# Populated_PLG_sensor.net
KiCad netlist of a schematic drawn in EAGLE
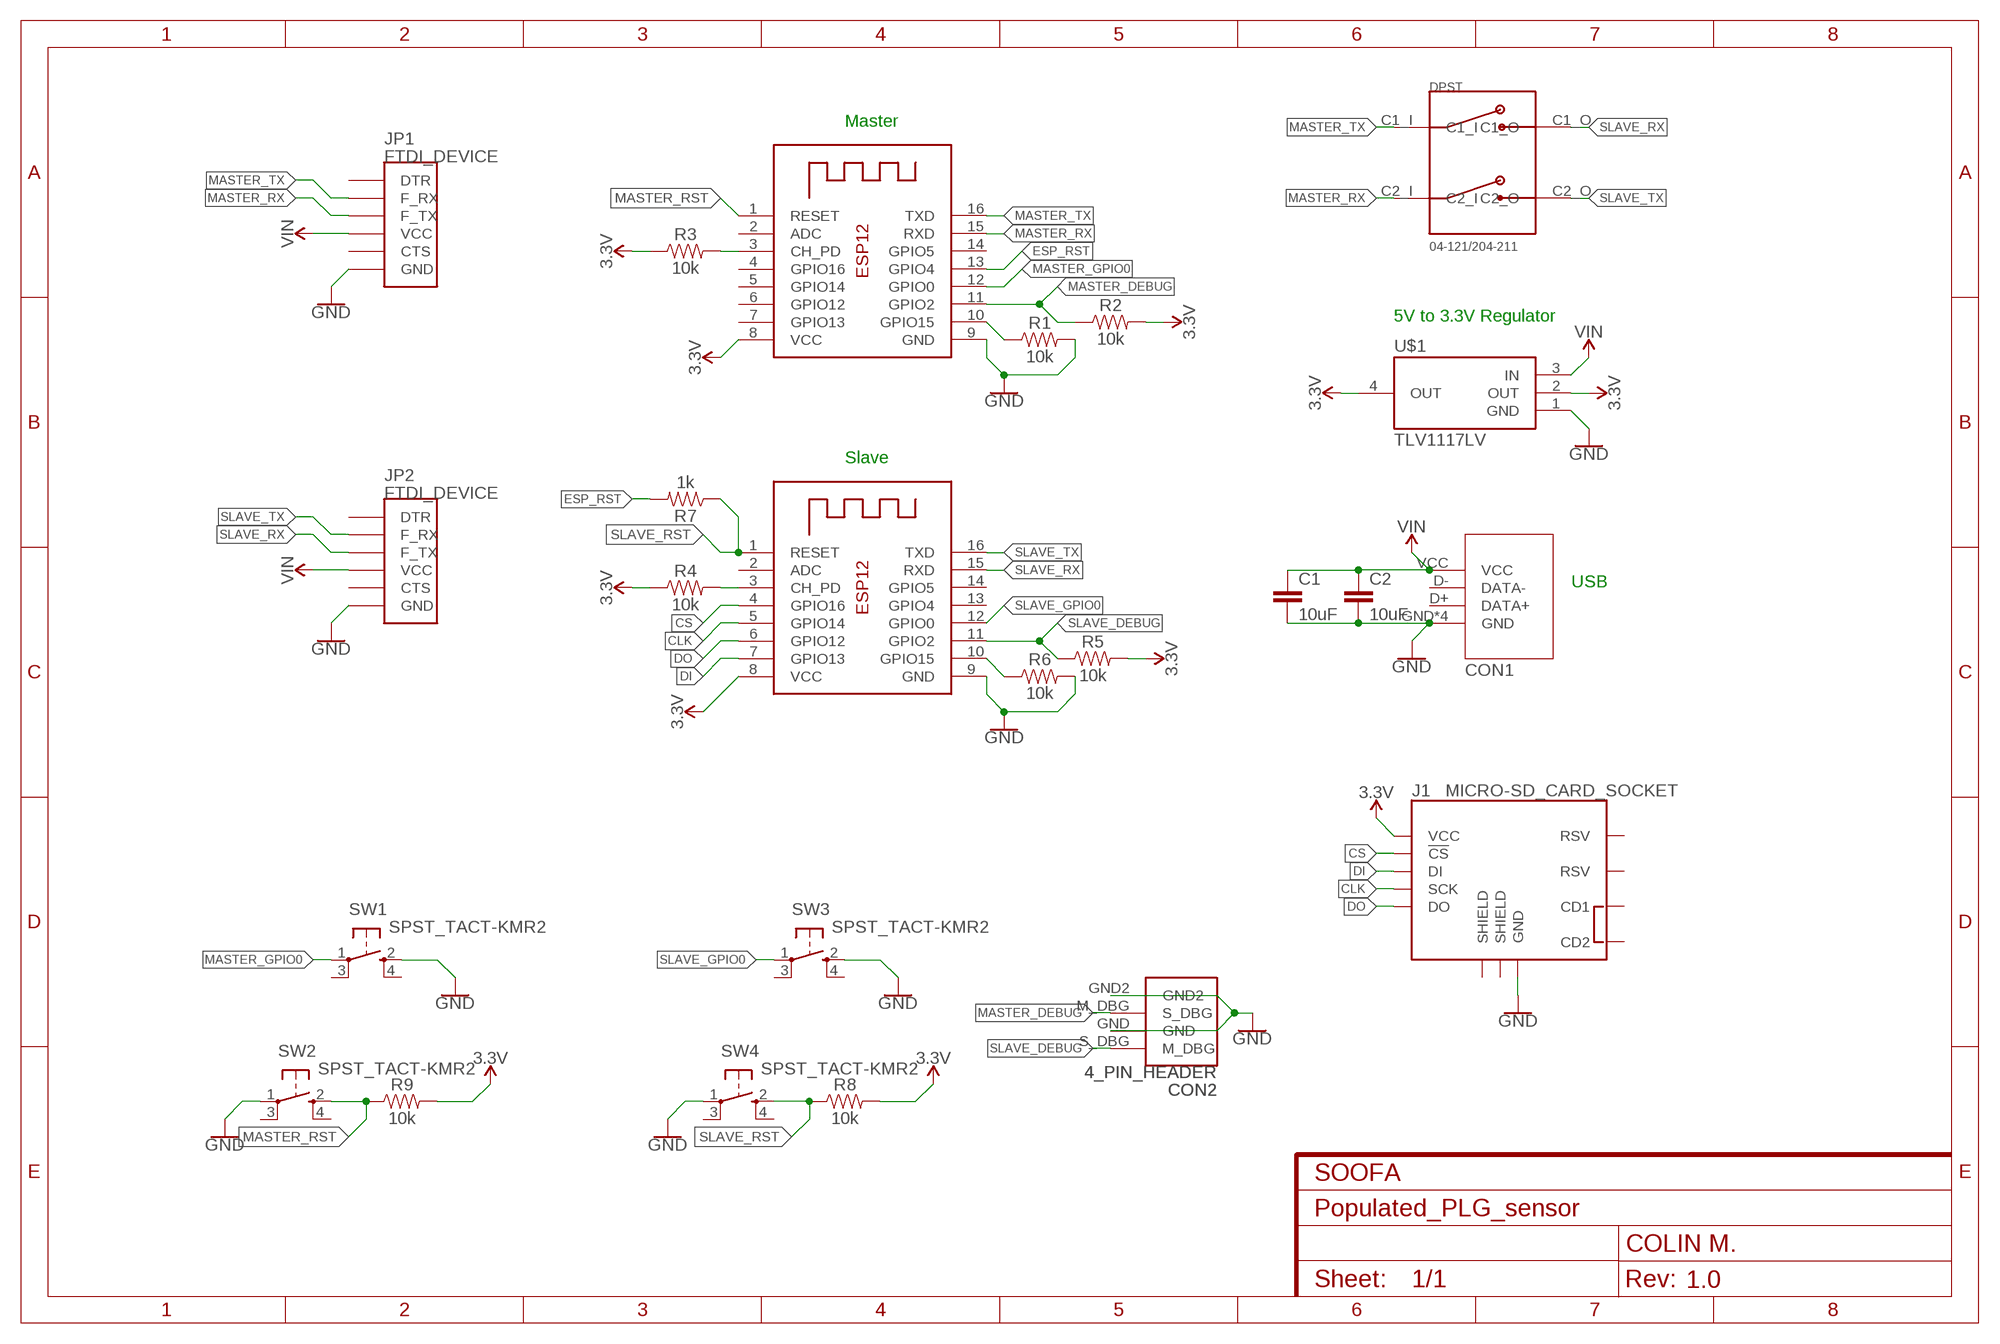
[diagram p0: schematic, sheet 1]

(export (version "E")
  (design (tool "Eeschema 10.0.6"))
  (components
    (comp (ref "C1")
      (value "10uF")
      (footprint "eagle-import:0603")
      (libsource (lib "eagle-import") (part "10UF-0603-6.3V-20%"))
    )
    (comp (ref "C2")
      (value "10uF")
      (footprint "eagle-import:0603")
      (libsource (lib "eagle-import") (part "10UF-0603-6.3V-20%"))
    )
    (comp (ref "CON1")
      (value "USB_MOLEX_0480372200")
      (footprint "eagle-import:USB_MOLEX_0480372200")
      (libsource (lib "eagle-import") (part "USB_MOLEX_0480372200"))
    )
    (comp (ref "CON2")
      (value "4_PIN_HEADER")
      (footprint "eagle-import:22-23-2041")
      (libsource (lib "eagle-import") (part "4_PIN_HEADER"))
    )
    (comp (ref "DPST1")
      (value "DPST_1POS")
      (footprint "eagle-import:DPST_1POS")
      (libsource (lib "eagle-import") (part "DPST_1POS"))
    )
    (comp (ref "J1")
      (value "MICRO-SD_CARD_SOCKET")
      (footprint "eagle-import:MICRO-SD-SOCKET")
      (libsource (lib "eagle-import") (part "MICRO-SD_CARD_SOCKET"))
    )
    (comp (ref "JP1")
      (value "FTDI_DEVICE")
      (footprint "eagle-import:FTDI_DEVICE_SIDE")
      (libsource (lib "eagle-import") (part "FTDI_DEVICE"))
    )
    (comp (ref "JP2")
      (value "FTDI_DEVICE")
      (footprint "eagle-import:FTDI_DEVICE_SIDE")
      (libsource (lib "eagle-import") (part "FTDI_DEVICE"))
    )
    (comp (ref "R1")
      (value "10k")
      (footprint "eagle-import:0603")
      (libsource (lib "eagle-import") (part "10KOHM-0603-1/10W-1%"))
    )
    (comp (ref "R2")
      (value "10k")
      (footprint "eagle-import:0603")
      (libsource (lib "eagle-import") (part "10KOHM-0603-1/10W-1%"))
    )
    (comp (ref "R3")
      (value "10k")
      (footprint "eagle-import:0603")
      (libsource (lib "eagle-import") (part "10KOHM-0603-1/10W-1%"))
    )
    (comp (ref "R4")
      (value "10k")
      (footprint "eagle-import:0603")
      (libsource (lib "eagle-import") (part "10KOHM-0603-1/10W-1%"))
    )
    (comp (ref "R5")
      (value "10k")
      (footprint "eagle-import:0603")
      (libsource (lib "eagle-import") (part "10KOHM-0603-1/10W-1%"))
    )
    (comp (ref "R6")
      (value "10k")
      (footprint "eagle-import:0603")
      (libsource (lib "eagle-import") (part "10KOHM-0603-1/10W-1%"))
    )
    (comp (ref "R7")
      (value "1k")
      (footprint "eagle-import:0603")
      (libsource (lib "eagle-import") (part "1KOHM-0603-1/10W-1%"))
    )
    (comp (ref "R8")
      (value "10k")
      (footprint "eagle-import:0603")
      (libsource (lib "eagle-import") (part "10KOHM-0603-1/10W-1%"))
    )
    (comp (ref "R9")
      (value "10k")
      (footprint "eagle-import:0603")
      (libsource (lib "eagle-import") (part "10KOHM-0603-1/10W-1%"))
    )
    (comp (ref "SW1")
      (value "SPST_TACT-KMR2")
      (footprint "eagle-import:KMR2")
      (libsource (lib "eagle-import") (part "SPST_TACT-KMR2"))
    )
    (comp (ref "SW2")
      (value "SPST_TACT-KMR2")
      (footprint "eagle-import:KMR2")
      (libsource (lib "eagle-import") (part "SPST_TACT-KMR2"))
    )
    (comp (ref "SW3")
      (value "SPST_TACT-KMR2")
      (footprint "eagle-import:KMR2")
      (libsource (lib "eagle-import") (part "SPST_TACT-KMR2"))
    )
    (comp (ref "SW4")
      (value "SPST_TACT-KMR2")
      (footprint "eagle-import:KMR2")
      (libsource (lib "eagle-import") (part "SPST_TACT-KMR2"))
    )
    (comp (ref "U$1")
      (value "TLV1117LV")
      (footprint "eagle-import:SOT223")
      (libsource (lib "eagle-import") (part "TLV1117LV"))
    )
    (comp (ref "X1")
      (value "ESP-12")
      (footprint "eagle-import:ESP-12")
      (libsource (lib "eagle-import") (part "ESP-12"))
    )
    (comp (ref "X2")
      (value "ESP-12")
      (footprint "eagle-import:ESP-12")
      (libsource (lib "eagle-import") (part "ESP-12"))
    )
  )
  (nets
    (net (code "1") (name "3.3V") (class "Default")
      (node (ref "J1") (pin "VCC") (pinfunction "VCC_VCC") (pintype "bidirectional"))
      (node (ref "R2") (pin "2") (pinfunction "2_2") (pintype "passive"))
      (node (ref "R3") (pin "1") (pinfunction "1_1") (pintype "passive"))
      (node (ref "R4") (pin "1") (pinfunction "1_1") (pintype "passive"))
      (node (ref "R5") (pin "2") (pinfunction "2_2") (pintype "passive"))
      (node (ref "R8") (pin "2") (pinfunction "2_2") (pintype "passive"))
      (node (ref "R9") (pin "2") (pinfunction "2_2") (pintype "passive"))
      (node (ref "U$1") (pin "2") (pinfunction "OUT_2") (pintype "bidirectional"))
      (node (ref "U$1") (pin "4") (pinfunction "OUT_4") (pintype "bidirectional"))
      (node (ref "X1") (pin "8") (pinfunction "VCC_8") (pintype "power_in"))
      (node (ref "X2") (pin "8") (pinfunction "VCC_8") (pintype "power_in"))
    )
    (net (code "2") (name "CLK") (class "Default")
      (node (ref "J1") (pin "SCLK") (pinfunction "SCK_SCLK") (pintype "bidirectional"))
      (node (ref "X2") (pin "5") (pinfunction "GPIO14_5") (pintype "bidirectional"))
    )
    (net (code "3") (name "CS") (class "Default")
      (node (ref "J1") (pin "CS") (pinfunction "~{CS}_CS") (pintype "bidirectional"))
      (node (ref "X2") (pin "4") (pinfunction "GPIO16_4") (pintype "bidirectional"))
    )
    (net (code "4") (name "DI") (class "Default")
      (node (ref "J1") (pin "DI") (pinfunction "DI_DI") (pintype "bidirectional"))
      (node (ref "X2") (pin "7") (pinfunction "GPIO13_7") (pintype "bidirectional"))
    )
    (net (code "5") (name "DO") (class "Default")
      (node (ref "J1") (pin "DO") (pinfunction "DO_DO") (pintype "bidirectional"))
      (node (ref "X2") (pin "6") (pinfunction "GPIO12_6") (pintype "bidirectional"))
    )
    (net (code "6") (name "ESP_RST") (class "Default")
      (node (ref "R7") (pin "2") (pinfunction "2_2") (pintype "passive"))
      (node (ref "X1") (pin "13") (pinfunction "GPIO4_13") (pintype "bidirectional"))
    )
    (net (code "7") (name "GND") (class "Default")
      (node (ref "C1") (pin "2") (pinfunction "2_2") (pintype "passive"))
      (node (ref "C2") (pin "2") (pinfunction "2_2") (pintype "passive"))
      (node (ref "CON1") (pin "GND") (pinfunction "GND_GND") (pintype "bidirectional"))
      (node (ref "CON1") (pin "GND2") (pinfunction "GND_GND2") (pintype "bidirectional"))
      (node (ref "CON1") (pin "GND3") (pinfunction "GND_GND3") (pintype "bidirectional"))
      (node (ref "CON1") (pin "GND4") (pinfunction "GND_GND4") (pintype "bidirectional"))
      (node (ref "CON2") (pin "GND") (pinfunction "GND_GND") (pintype "bidirectional"))
      (node (ref "CON2") (pin "GND2") (pinfunction "GND2_GND2") (pintype "bidirectional"))
      (node (ref "J1") (pin "GND") (pinfunction "GND_GND") (pintype "bidirectional"))
      (node (ref "JP1") (pin "P$6") (pinfunction "GND_P$6") (pintype "bidirectional"))
      (node (ref "JP2") (pin "P$6") (pinfunction "GND_P$6") (pintype "bidirectional"))
      (node (ref "R1") (pin "2") (pinfunction "2_2") (pintype "passive"))
      (node (ref "R6") (pin "2") (pinfunction "2_2") (pintype "passive"))
      (node (ref "SW1") (pin "2") (pinfunction "S_2") (pintype "passive"))
      (node (ref "SW2") (pin "1") (pinfunction "P_1") (pintype "passive"))
      (node (ref "SW3") (pin "2") (pinfunction "S_2") (pintype "passive"))
      (node (ref "SW4") (pin "1") (pinfunction "P_1") (pintype "passive"))
      (node (ref "U$1") (pin "1") (pinfunction "GND_1") (pintype "bidirectional"))
      (node (ref "X1") (pin "9") (pinfunction "GND_9") (pintype "power_in"))
      (node (ref "X2") (pin "9") (pinfunction "GND_9") (pintype "power_in"))
    )
    (net (code "8") (name "MASTER_DEBUG") (class "Default")
      (node (ref "CON2") (pin "M_DBG") (pinfunction "S_DBG_M_DBG") (pintype "bidirectional"))
      (node (ref "R2") (pin "1") (pinfunction "1_1") (pintype "passive"))
      (node (ref "X1") (pin "11") (pinfunction "GPIO2_11") (pintype "bidirectional"))
    )
    (net (code "9") (name "MASTER_GPIO0") (class "Default")
      (node (ref "SW1") (pin "1") (pinfunction "P_1") (pintype "passive"))
      (node (ref "X1") (pin "12") (pinfunction "GPIO0_12") (pintype "bidirectional"))
    )
    (net (code "10") (name "MASTER_RST") (class "Default")
      (node (ref "R9") (pin "1") (pinfunction "1_1") (pintype "passive"))
      (node (ref "SW2") (pin "2") (pinfunction "S_2") (pintype "passive"))
      (node (ref "X1") (pin "1") (pinfunction "RESET_1") (pintype "input"))
    )
    (net (code "11") (name "MASTER_RX") (class "Default")
      (node (ref "DPST1") (pin "C2_I") (pinfunction "C2_I_C2_I") (pintype "bidirectional"))
      (node (ref "JP1") (pin "P$3") (pinfunction "F_TX_P$3") (pintype "bidirectional"))
      (node (ref "X1") (pin "15") (pinfunction "RXD_15") (pintype "input"))
    )
    (net (code "12") (name "MASTER_TX") (class "Default")
      (node (ref "DPST1") (pin "C1_I") (pinfunction "C1_I_C1_I") (pintype "bidirectional"))
      (node (ref "JP1") (pin "P$2") (pinfunction "F_RX_P$2") (pintype "bidirectional"))
      (node (ref "X1") (pin "16") (pinfunction "TXD_16") (pintype "output"))
    )
    (net (code "13") (name "Net-(X1-CH_PD)") (class "Default")
      (node (ref "R3") (pin "2") (pinfunction "2_2") (pintype "passive"))
      (node (ref "X1") (pin "3") (pinfunction "CH_PD_3") (pintype "input"))
    )
    (net (code "14") (name "Net-(X1-GPIO15)") (class "Default")
      (node (ref "R1") (pin "1") (pinfunction "1_1") (pintype "passive"))
      (node (ref "X1") (pin "10") (pinfunction "GPIO15_10") (pintype "bidirectional"))
    )
    (net (code "15") (name "Net-(X2-CH_PD)") (class "Default")
      (node (ref "R4") (pin "2") (pinfunction "2_2") (pintype "passive"))
      (node (ref "X2") (pin "3") (pinfunction "CH_PD_3") (pintype "input"))
    )
    (net (code "16") (name "Net-(X2-GPIO15)") (class "Default")
      (node (ref "R6") (pin "1") (pinfunction "1_1") (pintype "passive"))
      (node (ref "X2") (pin "10") (pinfunction "GPIO15_10") (pintype "bidirectional"))
    )
    (net (code "17") (name "SLAVE_DEBUG") (class "Default")
      (node (ref "CON2") (pin "S_DBG") (pinfunction "M_DBG_S_DBG") (pintype "bidirectional"))
      (node (ref "R5") (pin "1") (pinfunction "1_1") (pintype "passive"))
      (node (ref "X2") (pin "11") (pinfunction "GPIO2_11") (pintype "bidirectional"))
    )
    (net (code "18") (name "SLAVE_GPIO0") (class "Default")
      (node (ref "SW3") (pin "1") (pinfunction "P_1") (pintype "passive"))
      (node (ref "X2") (pin "12") (pinfunction "GPIO0_12") (pintype "bidirectional"))
    )
    (net (code "19") (name "SLAVE_RST") (class "Default")
      (node (ref "R7") (pin "1") (pinfunction "1_1") (pintype "passive"))
      (node (ref "R8") (pin "1") (pinfunction "1_1") (pintype "passive"))
      (node (ref "SW4") (pin "2") (pinfunction "S_2") (pintype "passive"))
      (node (ref "X2") (pin "1") (pinfunction "RESET_1") (pintype "input"))
    )
    (net (code "20") (name "SLAVE_RX") (class "Default")
      (node (ref "DPST1") (pin "C1_O") (pinfunction "C1_O_C1_O") (pintype "bidirectional"))
      (node (ref "JP2") (pin "P$3") (pinfunction "F_TX_P$3") (pintype "bidirectional"))
      (node (ref "X2") (pin "15") (pinfunction "RXD_15") (pintype "input"))
    )
    (net (code "21") (name "SLAVE_TX") (class "Default")
      (node (ref "DPST1") (pin "C2_O") (pinfunction "C2_O_C2_O") (pintype "bidirectional"))
      (node (ref "JP2") (pin "P$2") (pinfunction "F_RX_P$2") (pintype "bidirectional"))
      (node (ref "X2") (pin "16") (pinfunction "TXD_16") (pintype "output"))
    )
    (net (code "22") (name "VIN") (class "Default")
      (node (ref "C1") (pin "1") (pinfunction "1_1") (pintype "passive"))
      (node (ref "C2") (pin "1") (pinfunction "1_1") (pintype "passive"))
      (node (ref "CON1") (pin "VCC") (pinfunction "VCC_VCC") (pintype "bidirectional"))
      (node (ref "JP1") (pin "P$4") (pinfunction "VCC_P$4") (pintype "bidirectional"))
      (node (ref "JP2") (pin "P$4") (pinfunction "VCC_P$4") (pintype "bidirectional"))
      (node (ref "U$1") (pin "3") (pinfunction "IN_3") (pintype "bidirectional"))
    )
    (net (code "23") (name "unconnected-(CON1-DATA+-PadD+)") (class "Default")
      (node (ref "CON1") (pin "D+") (pinfunction "DATA+_D+") (pintype "bidirectional"))
    )
    (net (code "24") (name "unconnected-(CON1-DATA--PadD-)") (class "Default")
      (node (ref "CON1") (pin "D-") (pinfunction "DATA-_D-") (pintype "bidirectional"))
    )
    (net (code "25") (name "unconnected-(J1-PadCD1)") (class "Default")
      (node (ref "J1") (pin "CD1") (pinfunction "CD1_CD1") (pintype "bidirectional"))
    )
    (net (code "26") (name "unconnected-(J1-PadCD2)") (class "Default")
      (node (ref "J1") (pin "CD2") (pinfunction "CD2_CD2") (pintype "bidirectional"))
    )
    (net (code "27") (name "unconnected-(J1-RSV-PadRSV1)") (class "Default")
      (node (ref "J1") (pin "RSV1") (pinfunction "RSV_RSV1") (pintype "bidirectional"))
    )
    (net (code "28") (name "unconnected-(J1-RSV-PadRSV2)") (class "Default")
      (node (ref "J1") (pin "RSV2") (pinfunction "RSV_RSV2") (pintype "bidirectional"))
    )
    (net (code "29") (name "unconnected-(J1-SHIELD-PadGND1)") (class "Default")
      (node (ref "J1") (pin "GND1") (pinfunction "SHIELD_GND1") (pintype "bidirectional"))
    )
    (net (code "30") (name "unconnected-(J1-SHIELD-PadGND3)") (class "Default")
      (node (ref "J1") (pin "GND3") (pinfunction "SHIELD_GND3") (pintype "bidirectional"))
    )
    (net (code "31") (name "unconnected-(JP1-CTS-PadP$5)") (class "Default")
      (node (ref "JP1") (pin "P$5") (pinfunction "CTS_P$5") (pintype "bidirectional"))
    )
    (net (code "32") (name "unconnected-(JP1-DTR-PadP$1)") (class "Default")
      (node (ref "JP1") (pin "P$1") (pinfunction "DTR_P$1") (pintype "bidirectional"))
    )
    (net (code "33") (name "unconnected-(JP2-CTS-PadP$5)") (class "Default")
      (node (ref "JP2") (pin "P$5") (pinfunction "CTS_P$5") (pintype "bidirectional"))
    )
    (net (code "34") (name "unconnected-(JP2-DTR-PadP$1)") (class "Default")
      (node (ref "JP2") (pin "P$1") (pinfunction "DTR_P$1") (pintype "bidirectional"))
    )
    (net (code "35") (name "unconnected-(SW1-P1-Pad3)") (class "Default")
      (node (ref "SW1") (pin "3") (pinfunction "P1_3") (pintype "passive"))
    )
    (net (code "36") (name "unconnected-(SW1-S1-Pad4)") (class "Default")
      (node (ref "SW1") (pin "4") (pinfunction "S1_4") (pintype "passive"))
    )
    (net (code "37") (name "unconnected-(SW2-P1-Pad3)") (class "Default")
      (node (ref "SW2") (pin "3") (pinfunction "P1_3") (pintype "passive"))
    )
    (net (code "38") (name "unconnected-(SW2-S1-Pad4)") (class "Default")
      (node (ref "SW2") (pin "4") (pinfunction "S1_4") (pintype "passive"))
    )
    (net (code "39") (name "unconnected-(SW3-P1-Pad3)") (class "Default")
      (node (ref "SW3") (pin "3") (pinfunction "P1_3") (pintype "passive"))
    )
    (net (code "40") (name "unconnected-(SW3-S1-Pad4)") (class "Default")
      (node (ref "SW3") (pin "4") (pinfunction "S1_4") (pintype "passive"))
    )
    (net (code "41") (name "unconnected-(SW4-P1-Pad3)") (class "Default")
      (node (ref "SW4") (pin "3") (pinfunction "P1_3") (pintype "passive"))
    )
    (net (code "42") (name "unconnected-(SW4-S1-Pad4)") (class "Default")
      (node (ref "SW4") (pin "4") (pinfunction "S1_4") (pintype "passive"))
    )
    (net (code "43") (name "unconnected-(X1-ADC-Pad2)") (class "Default")
      (node (ref "X1") (pin "2") (pinfunction "ADC_2") (pintype "passive"))
    )
    (net (code "44") (name "unconnected-(X1-GPIO5-Pad14)") (class "Default")
      (node (ref "X1") (pin "14") (pinfunction "GPIO5_14") (pintype "bidirectional"))
    )
    (net (code "45") (name "unconnected-(X1-GPIO12-Pad6)") (class "Default")
      (node (ref "X1") (pin "6") (pinfunction "GPIO12_6") (pintype "bidirectional"))
    )
    (net (code "46") (name "unconnected-(X1-GPIO13-Pad7)") (class "Default")
      (node (ref "X1") (pin "7") (pinfunction "GPIO13_7") (pintype "bidirectional"))
    )
    (net (code "47") (name "unconnected-(X1-GPIO14-Pad5)") (class "Default")
      (node (ref "X1") (pin "5") (pinfunction "GPIO14_5") (pintype "bidirectional"))
    )
    (net (code "48") (name "unconnected-(X1-GPIO16-Pad4)") (class "Default")
      (node (ref "X1") (pin "4") (pinfunction "GPIO16_4") (pintype "bidirectional"))
    )
    (net (code "49") (name "unconnected-(X2-ADC-Pad2)") (class "Default")
      (node (ref "X2") (pin "2") (pinfunction "ADC_2") (pintype "passive"))
    )
    (net (code "50") (name "unconnected-(X2-GPIO4-Pad13)") (class "Default")
      (node (ref "X2") (pin "13") (pinfunction "GPIO4_13") (pintype "bidirectional"))
    )
    (net (code "51") (name "unconnected-(X2-GPIO5-Pad14)") (class "Default")
      (node (ref "X2") (pin "14") (pinfunction "GPIO5_14") (pintype "bidirectional"))
    )
  )
)
